# eBox_3G_SIM.net
KiCad netlist of a schematic drawn in Altium Designer
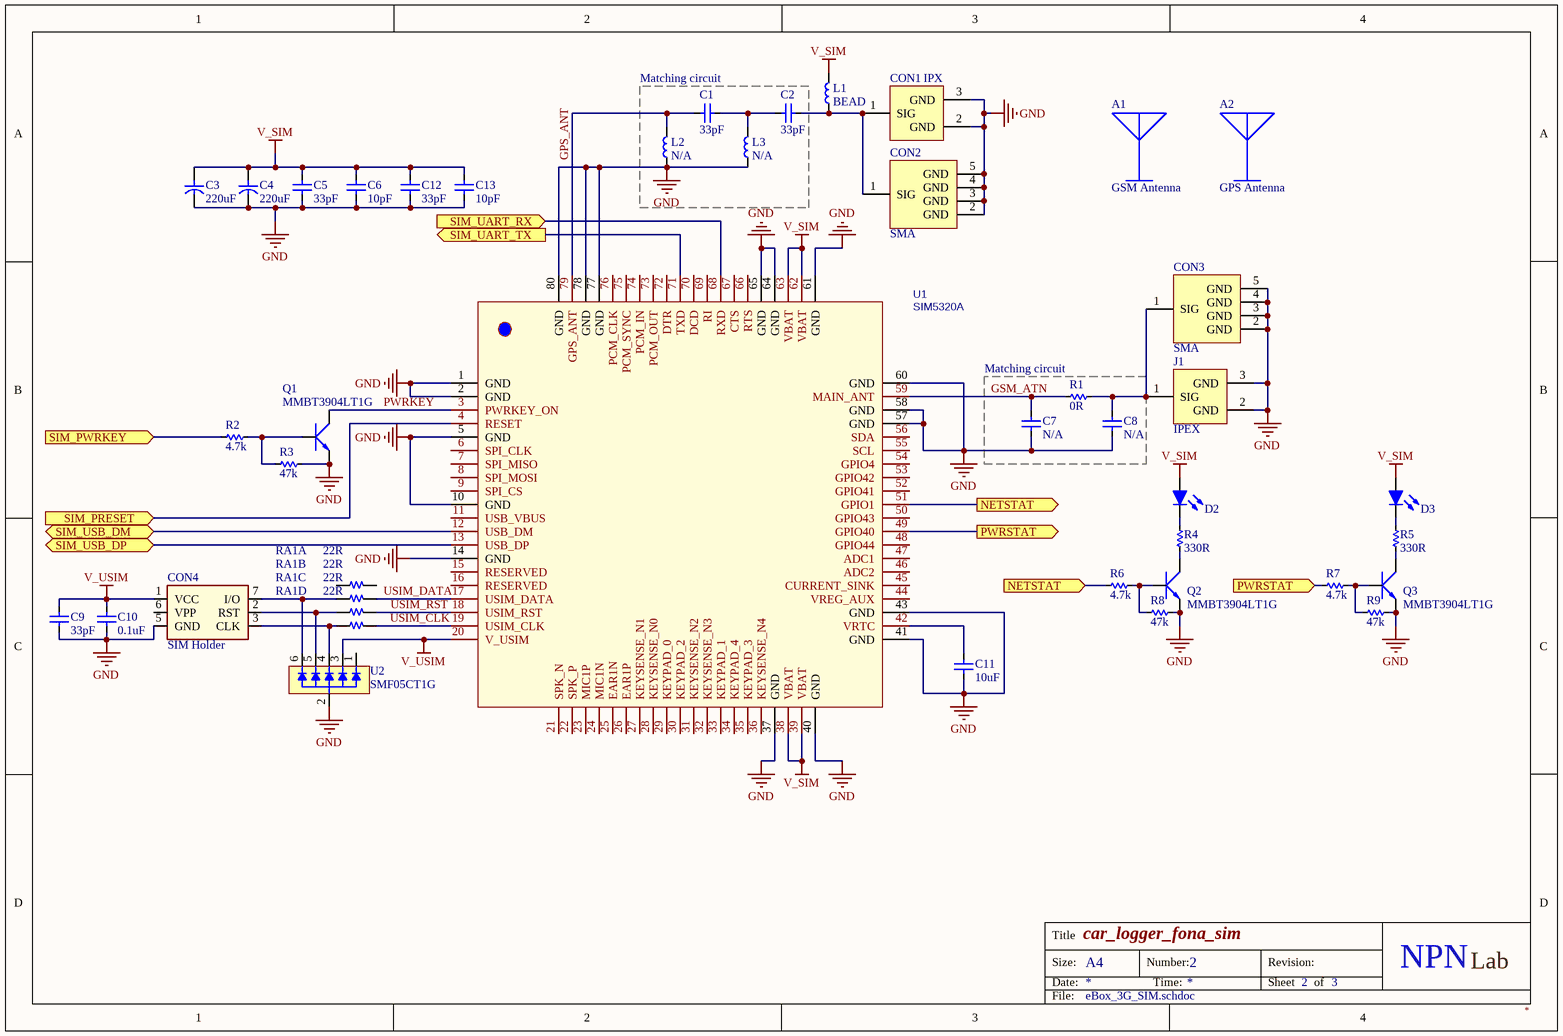
[diagram p0: eBox_3G_SIM.schdoc]

(export (version "E")
  (design (tool "Eeschema 10.0.6"))
  (components
    (comp (ref "A1")
      (value "GSM Antenna")
      (footprint "Antenna")
      (description "Antenna")
      (libsource (lib "car_logger_libs") (part "Antenna"))
    )
    (comp (ref "A2")
      (value "GPS Antenna")
      (footprint "Antenna")
      (description "Antenna")
      (libsource (lib "car_logger_libs") (part "Antenna"))
    )
    (comp (ref "C1")
      (value "33pF")
      (footprint "CC 0603")
      (description "CAP CER 33PF 100V C0G/NP0 0603")
      (fields
        (field (name "MANUFACTURER") "Murata Electronics")
        (field (name "MANUFACTURER PART NUMBER") "GCM1885C2A330JA16D")
      )
      (libsource (lib "car_logger_libs") (part "Capacitor NP"))
    )
    (comp (ref "C2")
      (value "33pF")
      (footprint "CC 0603")
      (description "CAP CER 33PF 100V C0G/NP0 0603")
      (fields
        (field (name "MANUFACTURER") "Murata Electronics")
        (field (name "MANUFACTURER PART NUMBER") "GCM1885C2A330JA16D")
      )
      (libsource (lib "car_logger_libs") (part "Capacitor NP"))
    )
    (comp (ref "C3")
      (value "220uF")
      (footprint "C SMD ALU (D8)")
      (description "CAP TANT POLY 100UF 6.3V 1210")
      (fields
        (field (name "MANUFACTURER") "AVX Corporation")
        (field (name "MANUFACTURER PART NUMBER") "TCJB107M006R0055")
      )
      (libsource (lib "ChipFC_Lib") (part "Capacitor"))
    )
    (comp (ref "C4")
      (value "220uF")
      (footprint "C SMD ALU (D8)")
      (description "CAP TANT POLY 100UF 6.3V 1210")
      (fields
        (field (name "MANUFACTURER") "AVX Corporation")
        (field (name "MANUFACTURER PART NUMBER") "TCJB107M006R0055")
      )
      (libsource (lib "ChipFC_Lib") (part "Capacitor"))
    )
    (comp (ref "C5")
      (value "33pF")
      (footprint "CC 0603")
      (description "CAP CER 33PF 100V C0G/NP0 0603")
      (fields
        (field (name "MANUFACTURER") "Murata Electronics")
        (field (name "MANUFACTURER PART NUMBER") "GCM1885C2A330JA16D")
      )
      (libsource (lib "car_logger_libs") (part "Capacitor NP"))
    )
    (comp (ref "C6")
      (value "10pF")
      (footprint "CC 0603")
      (description "CAP CER 10PF 100V C0G/NP0 0603")
      (fields
        (field (name "MANUFACTURER") "Murata Electronics")
        (field (name "MANUFACTURER PART NUMBER") "GCM1885C2A100JA16D")
      )
      (libsource (lib "car_logger_libs") (part "Capacitor NP"))
    )
    (comp (ref "C7")
      (value "N/A")
      (footprint "CC 0603")
      (description "CAP N/A")
      (libsource (lib "car_logger_libs") (part "Capacitor NP"))
    )
    (comp (ref "C8")
      (value "N/A")
      (footprint "CC 0603")
      (description "CAP N/A")
      (libsource (lib "car_logger_libs") (part "Capacitor NP"))
    )
    (comp (ref "C9")
      (value "33pF")
      (footprint "CC 0603")
      (description "CAP CER 33PF 100V C0G/NP0 0603")
      (fields
        (field (name "MANUFACTURER") "Murata Electronics")
        (field (name "MANUFACTURER PART NUMBER") "GCM1885C2A330JA16D")
      )
      (libsource (lib "car_logger_libs") (part "Capacitor NP"))
    )
    (comp (ref "C10")
      (value "0.1uF")
      (footprint "CC 0603")
      (description "CAP CER 0.1UF 16V X7R 0603")
      (fields
        (field (name "MANUFACTURER") "Murata Electronics")
        (field (name "MANUFACTURER PART NUMBER") "GCJ188R71C104KA01D")
      )
      (libsource (lib "car_logger_libs") (part "Capacitor NP"))
    )
    (comp (ref "C11")
      (value "10uF")
      (footprint "CC 0805")
      (description "CAP CER 10UF 10V X5R 0603")
      (fields
        (field (name "MANUFACTURER") "Murata Electronics")
        (field (name "MANUFACTURER PART NUMBER") "GRM188R61A106KE69D")
      )
      (libsource (lib "car_logger_libs") (part "Capacitor NP"))
    )
    (comp (ref "C12")
      (value "33pF")
      (footprint "CC 0603")
      (description "CAP CER 33PF 100V C0G/NP0 0603")
      (fields
        (field (name "MANUFACTURER") "Murata Electronics")
        (field (name "MANUFACTURER PART NUMBER") "GCM1885C2A330JA16D")
      )
      (libsource (lib "car_logger_libs") (part "Capacitor NP"))
    )
    (comp (ref "C13")
      (value "10pF")
      (footprint "CC 0603")
      (description "CAP CER 10PF 100V C0G/NP0 0603")
      (fields
        (field (name "MANUFACTURER") "Murata Electronics")
        (field (name "MANUFACTURER PART NUMBER") "GCM1885C2A100JA16D")
      )
      (libsource (lib "car_logger_libs") (part "Capacitor NP"))
    )
    (comp (ref "CON1")
      (value "IPX")
      (footprint "CONN/IPX/SMD")
      (libsource (lib "chipfc_altium_libs") (part "CON IPX"))
    )
    (comp (ref "CON2")
      (value "SMA")
      (footprint "CONN/SMA/RA")
      (description "SMA connectors")
      (libsource (lib "chipfc_altium_libs") (part "CON SMA"))
    )
    (comp (ref "CON3")
      (value "SMA")
      (footprint "CONN/SMA/RA")
      (description "SMA connectors")
      (libsource (lib "chipfc_altium_libs") (part "CON SMA"))
    )
    (comp (ref "CON4")
      (value "SIM Holder")
      (footprint "CON SIM Holder C707")
      (description "SIM Card holder, 6 pins")
      (libsource (lib "chipfc_altium_libs") (part "SIM holder 6 pin"))
    )
    (comp (ref "D2")
      (value "LED GREEN")
      (footprint "Led 0603 - green")
      (description "LED GREEN DIFFUSED 0603 SMD")
      (fields
        (field (name "MANUFACTURER") "Rohm Semiconductor")
        (field (name "MANUFACTURER PART NUMBER") "SML-D12P8WT86")
      )
      (libsource (lib "ChipFC_Lib") (part "Led"))
    )
    (comp (ref "D3")
      (value "LED RED")
      (footprint "Led 0603 - red")
      (description "LED RED DIFFUSED 0603 SMD")
      (fields
        (field (name "MANUFACTURER") "Rohm Semiconductor")
        (field (name "MANUFACTURER PART NUMBER") "SML-D12U8WT86")
      )
      (libsource (lib "ChipFC_Lib") (part "Led"))
    )
    (comp (ref "J1")
      (value "IPEX")
      (footprint "CONN/IPX/SMD")
      (description "CONN UMC RCPT STR 50 OHM SMD")
      (fields
        (field (name "MANUFACTURER") "Taoglas Limited")
        (field (name "MANUFACTURER PART NUMBER") "RECE.20279.001E.01")
      )
      (libsource (lib "ChipFC_Lib") (part "CON IPX"))
    )
    (comp (ref "L1")
      (value "BEAD")
      (footprint "LL 0603")
      (description "FERRITE BEAD 30 OHM 0603 1LN")
      (fields
        (field (name "MANUFACTURER") "Vishay Dale")
        (field (name "MANUFACTURER PART NUMBER") "ILBB0603ER300V")
      )
      (libsource (lib "car_logger_libs") (part "Inductor"))
    )
    (comp (ref "L2")
      (value "N/A")
      (footprint "LL 0603")
      (description "IND N/A")
      (libsource (lib "car_logger_libs") (part "Inductor"))
    )
    (comp (ref "L3")
      (value "N/A")
      (footprint "LL 0603")
      (description "IND N/A")
      (libsource (lib "car_logger_libs") (part "Inductor"))
    )
    (comp (ref "Q1")
      (value "MMBT3904LT1G")
      (footprint "SOT-23")
      (description "TRANS NPN 40V 0.2A SOT23")
      (fields (field (name "MANUFACTURER") "ON Semiconductor"))
      (libsource (lib "car_logger_libs") (part "MMBT3904LT1G"))
    )
    (comp (ref "Q2")
      (value "MMBT3904LT1G")
      (footprint "SOT-23")
      (description "TRANS NPN 40V 0.2A SOT23")
      (fields (field (name "MANUFACTURER") "ON Semiconductor"))
      (libsource (lib "car_logger_libs") (part "MMBT3904LT1G"))
    )
    (comp (ref "Q3")
      (value "MMBT3904LT1G")
      (footprint "SOT-23")
      (description "TRANS NPN 40V 0.2A SOT23")
      (fields (field (name "MANUFACTURER") "ON Semiconductor"))
      (libsource (lib "car_logger_libs") (part "MMBT3904LT1G"))
    )
    (comp (ref "R1")
      (value "0R")
      (footprint "RR 0603")
      (description "RES SMD 0 OHM JUMPER 1/10W 0603")
      (fields
        (field (name "MANUFACTURER") "Panasonic Industrial Devices")
        (field (name "MANUFACTURER PART NUMBER") "ERJ-3GEY0R00V")
      )
      (libsource (lib "car_logger_libs") (part "Resistors"))
    )
    (comp (ref "R2")
      (value "4.7k")
      (footprint "RR 0603")
      (description "RES SMD 4.7K OHM 1% 1/10W 0603")
      (fields
        (field (name "MANUFACTURER") "Panasonic Industrial Devices")
        (field (name "MANUFACTURER PART NUMBER") "ERJ-3EKF4701V")
      )
      (libsource (lib "car_logger_libs") (part "Resistors"))
    )
    (comp (ref "R3")
      (value "47k")
      (footprint "RR 0603")
      (description "RES SMD 47K OHM 5% 1/10W 0603")
      (fields
        (field (name "MANUFACTURER") "Panasonic Industrial Devices")
        (field (name "MANUFACTURER PART NUMBER") "ERJ-3GEYJ473V")
      )
      (libsource (lib "car_logger_libs") (part "Resistors"))
    )
    (comp (ref "R4")
      (value "330R")
      (footprint "RR 0603")
      (description "RES SMD 330 OHM 5% 1/10W 0603")
      (fields
        (field (name "MANUFACTURER") "Panasonic Industrial Devices")
        (field (name "MANUFACTURER PART NUMBER") "ERJ-3GEYJ331V")
      )
      (libsource (lib "car_logger_libs") (part "Resistors"))
    )
    (comp (ref "R5")
      (value "330R")
      (footprint "RR 0603")
      (description "RES SMD 330 OHM 5% 1/10W 0603")
      (fields
        (field (name "MANUFACTURER") "Panasonic Industrial Devices")
        (field (name "MANUFACTURER PART NUMBER") "ERJ-3GEYJ331V")
      )
      (libsource (lib "car_logger_libs") (part "Resistors"))
    )
    (comp (ref "R6")
      (value "4.7k")
      (footprint "RR 0603")
      (description "RES SMD 4.7K OHM 1% 1/10W 0603")
      (fields
        (field (name "MANUFACTURER") "Panasonic Industrial Devices")
        (field (name "MANUFACTURER PART NUMBER") "ERJ-3EKF4701V")
      )
      (libsource (lib "car_logger_libs") (part "Resistors"))
    )
    (comp (ref "R7")
      (value "4.7k")
      (footprint "RR 0603")
      (description "RES SMD 4.7K OHM 1% 1/10W 0603")
      (fields
        (field (name "MANUFACTURER") "Panasonic Industrial Devices")
        (field (name "MANUFACTURER PART NUMBER") "ERJ-3EKF4701V")
      )
      (libsource (lib "car_logger_libs") (part "Resistors"))
    )
    (comp (ref "R8")
      (value "47k")
      (footprint "RR 0603")
      (description "RES SMD 47K OHM 5% 1/10W 0603")
      (fields
        (field (name "MANUFACTURER") "Panasonic Industrial Devices")
        (field (name "MANUFACTURER PART NUMBER") "ERJ-3GEYJ473V")
      )
      (libsource (lib "car_logger_libs") (part "Resistors"))
    )
    (comp (ref "R9")
      (value "47k")
      (footprint "RR 0603")
      (description "RES SMD 47K OHM 5% 1/10W 0603")
      (fields
        (field (name "MANUFACTURER") "Panasonic Industrial Devices")
        (field (name "MANUFACTURER PART NUMBER") "ERJ-3GEYJ473V")
      )
      (libsource (lib "car_logger_libs") (part "Resistors"))
    )
    (comp (ref "RA1")
      (value "22R")
      (footprint "RAx4 1206 (3216)")
      (libsource (lib "chipfc_altium_libs") (part "Resistor Array x4"))
    )
    (comp (ref "U1")
      (value "SIM5320A")
      (footprint "SIM5320")
      (libsource (lib "car_logger_libs") (part "SIM5320A"))
    )
    (comp (ref "U2")
      (value "SMF05CT1G")
      (footprint "SOT-363-6")
      (description "TVS DIODE 5V 12.5V SC88")
      (fields (field (name "MANUFACTURER") "ON Semiconductor"))
      (libsource (lib "car_logger_libs") (part "SMF05C"))
    )
  )
  (nets
    (net (code "1") (name "/GPS_ANT") (class "Default")
      (node (ref "C1") (pin "2") (pinfunction "2_2") (pintype "passive"))
      (node (ref "L2") (pin "2") (pinfunction "2_2") (pintype "passive"))
      (node (ref "U1") (pin "79") (pinfunction "GPS_ANT_79") (pintype "passive"))
    )
    (net (code "2") (name "/GSM_ATN") (class "Default")
      (node (ref "C7") (pin "2") (pinfunction "2_2") (pintype "passive"))
      (node (ref "R1") (pin "2") (pinfunction "2_2") (pintype "passive"))
      (node (ref "U1") (pin "59") (pinfunction "MAIN_ANT_59") (pintype "passive"))
    )
    (net (code "3") (name "/NETSTAT") (class "Default")
      (node (ref "R6") (pin "1") (pinfunction "1_1") (pintype "passive"))
      (node (ref "U1") (pin "51") (pinfunction "GPIO1_51") (pintype "passive"))
    )
    (net (code "4") (name "/PWRKEY") (class "Default")
      (node (ref "Q1") (pin "3") (pinfunction "C_3") (pintype "passive"))
      (node (ref "U1") (pin "3") (pinfunction "PWRKEY_ON_3") (pintype "passive"))
    )
    (net (code "5") (name "/PWRSTAT") (class "Default")
      (node (ref "R7") (pin "1") (pinfunction "1_1") (pintype "passive"))
      (node (ref "U1") (pin "49") (pinfunction "GPIO40_49") (pintype "passive"))
    )
    (net (code "6") (name "/SIM_PRESET") (class "Default")
      (node (ref "U1") (pin "4") (pinfunction "RESET_4") (pintype "passive"))
    )
    (net (code "7") (name "/SIM_PWRKEY") (class "Default")
      (node (ref "R2") (pin "1") (pinfunction "1_1") (pintype "passive"))
    )
    (net (code "8") (name "/SIM_UART_RX") (class "Default")
      (node (ref "U1") (pin "68") (pinfunction "RXD_68") (pintype "passive"))
    )
    (net (code "9") (name "/SIM_UART_TX") (class "Default")
      (node (ref "U1") (pin "71") (pinfunction "TXD_71") (pintype "passive"))
    )
    (net (code "10") (name "/SIM_USB_DM") (class "Default")
      (node (ref "U1") (pin "12") (pinfunction "USB_DM_12") (pintype "passive"))
    )
    (net (code "11") (name "/SIM_USB_DP") (class "Default")
      (node (ref "U1") (pin "13") (pinfunction "USB_DP_13") (pintype "passive"))
    )
    (net (code "12") (name "/USIM_CLK") (class "Default")
      (node (ref "RA1") (pin "5") (pinfunction "5_5") (pintype "passive"))
      (node (ref "U1") (pin "19") (pinfunction "USIM_CLK_19") (pintype "passive"))
    )
    (net (code "13") (name "/USIM_DATA") (class "Default")
      (node (ref "RA1") (pin "7") (pinfunction "7_7") (pintype "passive"))
      (node (ref "U1") (pin "17") (pinfunction "USIM_DATA_17") (pintype "passive"))
    )
    (net (code "14") (name "/USIM_RST") (class "Default")
      (node (ref "RA1") (pin "6") (pinfunction "6_6") (pintype "passive"))
      (node (ref "U1") (pin "18") (pinfunction "USIM_RST_18") (pintype "passive"))
    )
    (net (code "15") (name "GND") (class "Default")
      (node (ref "C10") (pin "2") (pinfunction "2_2") (pintype "passive"))
      (node (ref "C11") (pin "1") (pinfunction "1_1") (pintype "passive"))
      (node (ref "C12") (pin "1") (pinfunction "1_1") (pintype "passive"))
      (node (ref "C13") (pin "1") (pinfunction "1_1") (pintype "passive"))
      (node (ref "C3") (pin "2") (pinfunction "2_2") (pintype "passive"))
      (node (ref "C4") (pin "2") (pinfunction "2_2") (pintype "passive"))
      (node (ref "C5") (pin "1") (pinfunction "1_1") (pintype "passive"))
      (node (ref "C6") (pin "1") (pinfunction "1_1") (pintype "passive"))
      (node (ref "C7") (pin "1") (pinfunction "1_1") (pintype "passive"))
      (node (ref "C8") (pin "1") (pinfunction "1_1") (pintype "passive"))
      (node (ref "C9") (pin "2") (pinfunction "2_2") (pintype "passive"))
      (node (ref "CON1") (pin "2") (pinfunction "GND_2") (pintype "passive"))
      (node (ref "CON1") (pin "3") (pinfunction "GND_3") (pintype "passive"))
      (node (ref "CON2") (pin "2") (pinfunction "GND_2") (pintype "passive"))
      (node (ref "CON2") (pin "3") (pinfunction "GND_3") (pintype "passive"))
      (node (ref "CON2") (pin "4") (pinfunction "GND_4") (pintype "passive"))
      (node (ref "CON2") (pin "5") (pinfunction "GND_5") (pintype "passive"))
      (node (ref "CON3") (pin "2") (pinfunction "GND_2") (pintype "passive"))
      (node (ref "CON3") (pin "3") (pinfunction "GND_3") (pintype "passive"))
      (node (ref "CON3") (pin "4") (pinfunction "GND_4") (pintype "passive"))
      (node (ref "CON3") (pin "5") (pinfunction "GND_5") (pintype "passive"))
      (node (ref "CON4") (pin "5") (pinfunction "GND_5") (pintype "power_in"))
      (node (ref "J1") (pin "2") (pinfunction "GND_2") (pintype "passive"))
      (node (ref "J1") (pin "3") (pinfunction "GND_3") (pintype "passive"))
      (node (ref "L2") (pin "1") (pinfunction "1_1") (pintype "passive"))
      (node (ref "L3") (pin "1") (pinfunction "1_1") (pintype "passive"))
      (node (ref "Q1") (pin "2") (pinfunction "E_2") (pintype "passive"))
      (node (ref "Q2") (pin "2") (pinfunction "E_2") (pintype "passive"))
      (node (ref "Q3") (pin "2") (pinfunction "E_2") (pintype "passive"))
      (node (ref "R3") (pin "2") (pinfunction "2_2") (pintype "passive"))
      (node (ref "R8") (pin "2") (pinfunction "2_2") (pintype "passive"))
      (node (ref "R9") (pin "2") (pinfunction "2_2") (pintype "passive"))
      (node (ref "U1") (pin "1") (pinfunction "GND_1") (pintype "passive"))
      (node (ref "U1") (pin "10") (pinfunction "GND_10") (pintype "passive"))
      (node (ref "U1") (pin "14") (pinfunction "GND_14") (pintype "passive"))
      (node (ref "U1") (pin "2") (pinfunction "GND_2") (pintype "passive"))
      (node (ref "U1") (pin "37") (pinfunction "GND_37") (pintype "passive"))
      (node (ref "U1") (pin "40") (pinfunction "GND_40") (pintype "passive"))
      (node (ref "U1") (pin "41") (pinfunction "GND_41") (pintype "passive"))
      (node (ref "U1") (pin "43") (pinfunction "GND_43") (pintype "passive"))
      (node (ref "U1") (pin "5") (pinfunction "GND_5") (pintype "passive"))
      (node (ref "U1") (pin "57") (pinfunction "GND_57") (pintype "passive"))
      (node (ref "U1") (pin "58") (pinfunction "GND_58") (pintype "passive"))
      (node (ref "U1") (pin "60") (pinfunction "GND_60") (pintype "passive"))
      (node (ref "U1") (pin "61") (pinfunction "GND_61") (pintype "passive"))
      (node (ref "U1") (pin "64") (pinfunction "GND_64") (pintype "passive"))
      (node (ref "U1") (pin "65") (pinfunction "GND_65") (pintype "passive"))
      (node (ref "U1") (pin "77") (pinfunction "GND_77") (pintype "passive"))
      (node (ref "U1") (pin "78") (pinfunction "GND_78") (pintype "passive"))
      (node (ref "U1") (pin "80") (pinfunction "GND_80") (pintype "passive"))
      (node (ref "U2") (pin "2") (pinfunction "A_2") (pintype "passive"))
    )
    (net (code "16") (name "Net-(C1-Pad1)") (class "Default")
      (node (ref "C1") (pin "1") (pinfunction "1_1") (pintype "passive"))
      (node (ref "C2") (pin "2") (pinfunction "2_2") (pintype "passive"))
      (node (ref "L3") (pin "2") (pinfunction "2_2") (pintype "passive"))
    )
    (net (code "17") (name "Net-(CON1-SIG)") (class "Default")
      (node (ref "C2") (pin "1") (pinfunction "1_1") (pintype "passive"))
      (node (ref "CON1") (pin "1") (pinfunction "SIG_1") (pintype "passive"))
      (node (ref "CON2") (pin "1") (pinfunction "SIG_1") (pintype "passive"))
      (node (ref "L1") (pin "1") (pinfunction "1_1") (pintype "passive"))
    )
    (net (code "18") (name "Net-(CON3-SIG)") (class "Default")
      (node (ref "C8") (pin "2") (pinfunction "2_2") (pintype "passive"))
      (node (ref "CON3") (pin "1") (pinfunction "SIG_1") (pintype "passive"))
      (node (ref "J1") (pin "1") (pinfunction "SIG_1") (pintype "passive"))
      (node (ref "R1") (pin "1") (pinfunction "1_1") (pintype "passive"))
    )
    (net (code "19") (name "Net-(CON4-CLK)") (class "Default")
      (node (ref "CON4") (pin "3") (pinfunction "CLK_3") (pintype "passive"))
      (node (ref "RA1") (pin "4") (pinfunction "4_4") (pintype "passive"))
      (node (ref "U2") (pin "4") (pinfunction "K4_4") (pintype "passive"))
    )
    (net (code "20") (name "Net-(CON4-I{slash}O)") (class "Default")
      (node (ref "CON4") (pin "7") (pinfunction "I/O_7") (pintype "passive"))
      (node (ref "RA1") (pin "2") (pinfunction "2_2") (pintype "passive"))
      (node (ref "U2") (pin "6") (pinfunction "K6_6") (pintype "passive"))
    )
    (net (code "21") (name "Net-(CON4-RST)") (class "Default")
      (node (ref "CON4") (pin "2") (pinfunction "RST_2") (pintype "passive"))
      (node (ref "RA1") (pin "3") (pinfunction "3_3") (pintype "passive"))
      (node (ref "U2") (pin "5") (pinfunction "K5_5") (pintype "passive"))
    )
    (net (code "22") (name "Net-(D2-K)") (class "Default")
      (node (ref "D2") (pin "2") (pinfunction "K_2") (pintype "passive"))
      (node (ref "R4") (pin "2") (pinfunction "2_2") (pintype "passive"))
    )
    (net (code "23") (name "Net-(D3-K)") (class "Default")
      (node (ref "D3") (pin "2") (pinfunction "K_2") (pintype "passive"))
      (node (ref "R5") (pin "2") (pinfunction "2_2") (pintype "passive"))
    )
    (net (code "24") (name "Net-(Q1-B)") (class "Default")
      (node (ref "Q1") (pin "1") (pinfunction "B_1") (pintype "passive"))
      (node (ref "R2") (pin "2") (pinfunction "2_2") (pintype "passive"))
      (node (ref "R3") (pin "1") (pinfunction "1_1") (pintype "passive"))
    )
    (net (code "25") (name "Net-(Q2-B)") (class "Default")
      (node (ref "Q2") (pin "1") (pinfunction "B_1") (pintype "passive"))
      (node (ref "R6") (pin "2") (pinfunction "2_2") (pintype "passive"))
      (node (ref "R8") (pin "1") (pinfunction "1_1") (pintype "passive"))
    )
    (net (code "26") (name "Net-(Q2-C)") (class "Default")
      (node (ref "Q2") (pin "3") (pinfunction "C_3") (pintype "passive"))
      (node (ref "R4") (pin "1") (pinfunction "1_1") (pintype "passive"))
    )
    (net (code "27") (name "Net-(Q3-B)") (class "Default")
      (node (ref "Q3") (pin "1") (pinfunction "B_1") (pintype "passive"))
      (node (ref "R7") (pin "2") (pinfunction "2_2") (pintype "passive"))
      (node (ref "R9") (pin "1") (pinfunction "1_1") (pintype "passive"))
    )
    (net (code "28") (name "Net-(Q3-C)") (class "Default")
      (node (ref "Q3") (pin "3") (pinfunction "C_3") (pintype "passive"))
      (node (ref "R5") (pin "1") (pinfunction "1_1") (pintype "passive"))
    )
    (net (code "29") (name "Net-(U1-VRTC)") (class "Default")
      (node (ref "C11") (pin "2") (pinfunction "2_2") (pintype "passive"))
      (node (ref "U1") (pin "42") (pinfunction "VRTC_42") (pintype "passive"))
    )
    (net (code "30") (name "V_SIM") (class "Default")
      (node (ref "C12") (pin "2") (pinfunction "2_2") (pintype "passive"))
      (node (ref "C13") (pin "2") (pinfunction "2_2") (pintype "passive"))
      (node (ref "C3") (pin "1") (pinfunction "1_1") (pintype "passive"))
      (node (ref "C4") (pin "1") (pinfunction "1_1") (pintype "passive"))
      (node (ref "C5") (pin "2") (pinfunction "2_2") (pintype "passive"))
      (node (ref "C6") (pin "2") (pinfunction "2_2") (pintype "passive"))
      (node (ref "D2") (pin "1") (pinfunction "A_1") (pintype "passive"))
      (node (ref "D3") (pin "1") (pinfunction "A_1") (pintype "passive"))
      (node (ref "L1") (pin "2") (pinfunction "2_2") (pintype "passive"))
      (node (ref "U1") (pin "38") (pinfunction "VBAT_38") (pintype "passive"))
      (node (ref "U1") (pin "39") (pinfunction "VBAT_39") (pintype "passive"))
      (node (ref "U1") (pin "62") (pinfunction "VBAT_62") (pintype "passive"))
      (node (ref "U1") (pin "63") (pinfunction "VBAT_63") (pintype "passive"))
    )
    (net (code "31") (name "V_USIM") (class "Default")
      (node (ref "C10") (pin "1") (pinfunction "1_1") (pintype "passive"))
      (node (ref "C9") (pin "1") (pinfunction "1_1") (pintype "passive"))
      (node (ref "CON4") (pin "1") (pinfunction "VCC_1") (pintype "power_in"))
      (node (ref "U1") (pin "20") (pinfunction "V_USIM_20") (pintype "passive"))
      (node (ref "U2") (pin "3") (pinfunction "K3_3") (pintype "passive"))
    )
    (net (code "32") (name "unconnected-(CON4-VPP-Pad6)") (class "Default")
      (node (ref "CON4") (pin "6") (pinfunction "VPP_6") (pintype "passive"))
    )
    (net (code "33") (name "unconnected-(RA1-Pad1)") (class "Default")
      (node (ref "RA1") (pin "1") (pinfunction "1_1") (pintype "passive"))
    )
    (net (code "34") (name "unconnected-(RA1-Pad8)") (class "Default")
      (node (ref "RA1") (pin "8") (pinfunction "8_8") (pintype "passive"))
    )
    (net (code "35") (name "unconnected-(U1-ADC1-Pad47)") (class "Default")
      (node (ref "U1") (pin "47") (pinfunction "ADC1_47") (pintype "passive"))
    )
    (net (code "36") (name "unconnected-(U1-ADC2-Pad46)") (class "Default")
      (node (ref "U1") (pin "46") (pinfunction "ADC2_46") (pintype "passive"))
    )
    (net (code "37") (name "unconnected-(U1-CTS-Pad67)") (class "Default")
      (node (ref "U1") (pin "67") (pinfunction "CTS_67") (pintype "passive"))
    )
    (net (code "38") (name "unconnected-(U1-CURRENT_SINK-Pad45)") (class "Default")
      (node (ref "U1") (pin "45") (pinfunction "CURRENT_SINK_45") (pintype "passive"))
    )
    (net (code "39") (name "unconnected-(U1-DCD-Pad70)") (class "Default")
      (node (ref "U1") (pin "70") (pinfunction "DCD_70") (pintype "passive"))
    )
    (net (code "40") (name "unconnected-(U1-DTR-Pad72)") (class "Default")
      (node (ref "U1") (pin "72") (pinfunction "DTR_72") (pintype "passive"))
    )
    (net (code "41") (name "unconnected-(U1-EAR1N-Pad25)") (class "Default")
      (node (ref "U1") (pin "25") (pinfunction "EAR1N_25") (pintype "passive"))
    )
    (net (code "42") (name "unconnected-(U1-EAR1P-Pad26)") (class "Default")
      (node (ref "U1") (pin "26") (pinfunction "EAR1P_26") (pintype "passive"))
    )
    (net (code "43") (name "unconnected-(U1-GPIO4-Pad54)") (class "Default")
      (node (ref "U1") (pin "54") (pinfunction "GPIO4_54") (pintype "passive"))
    )
    (net (code "44") (name "unconnected-(U1-GPIO41-Pad52)") (class "Default")
      (node (ref "U1") (pin "52") (pinfunction "GPIO41_52") (pintype "passive"))
    )
    (net (code "45") (name "unconnected-(U1-GPIO42-Pad53)") (class "Default")
      (node (ref "U1") (pin "53") (pinfunction "GPIO42_53") (pintype "passive"))
    )
    (net (code "46") (name "unconnected-(U1-GPIO43-Pad50)") (class "Default")
      (node (ref "U1") (pin "50") (pinfunction "GPIO43_50") (pintype "passive"))
    )
    (net (code "47") (name "unconnected-(U1-GPIO44-Pad48)") (class "Default")
      (node (ref "U1") (pin "48") (pinfunction "GPIO44_48") (pintype "passive"))
    )
    (net (code "48") (name "unconnected-(U1-KEYPAD_0-Pad29)") (class "Default")
      (node (ref "U1") (pin "29") (pinfunction "KEYPAD_0_29") (pintype "passive"))
    )
    (net (code "49") (name "unconnected-(U1-KEYPAD_1-Pad33)") (class "Default")
      (node (ref "U1") (pin "33") (pinfunction "KEYPAD_1_33") (pintype "passive"))
    )
    (net (code "50") (name "unconnected-(U1-KEYPAD_2-Pad30)") (class "Default")
      (node (ref "U1") (pin "30") (pinfunction "KEYPAD_2_30") (pintype "passive"))
    )
    (net (code "51") (name "unconnected-(U1-KEYPAD_3-Pad35)") (class "Default")
      (node (ref "U1") (pin "35") (pinfunction "KEYPAD_3_35") (pintype "passive"))
    )
    (net (code "52") (name "unconnected-(U1-KEYPAD_4-Pad34)") (class "Default")
      (node (ref "U1") (pin "34") (pinfunction "KEYPAD_4_34") (pintype "passive"))
    )
    (net (code "53") (name "unconnected-(U1-KEYSENSE_N0-Pad28)") (class "Default")
      (node (ref "U1") (pin "28") (pinfunction "KEYSENSE_N0_28") (pintype "passive"))
    )
    (net (code "54") (name "unconnected-(U1-KEYSENSE_N1-Pad27)") (class "Default")
      (node (ref "U1") (pin "27") (pinfunction "KEYSENSE_N1_27") (pintype "passive"))
    )
    (net (code "55") (name "unconnected-(U1-KEYSENSE_N2-Pad31)") (class "Default")
      (node (ref "U1") (pin "31") (pinfunction "KEYSENSE_N2_31") (pintype "passive"))
    )
    (net (code "56") (name "unconnected-(U1-KEYSENSE_N3-Pad32)") (class "Default")
      (node (ref "U1") (pin "32") (pinfunction "KEYSENSE_N3_32") (pintype "passive"))
    )
    (net (code "57") (name "unconnected-(U1-KEYSENSE_N4-Pad36)") (class "Default")
      (node (ref "U1") (pin "36") (pinfunction "KEYSENSE_N4_36") (pintype "passive"))
    )
    (net (code "58") (name "unconnected-(U1-MIC1N-Pad24)") (class "Default")
      (node (ref "U1") (pin "24") (pinfunction "MIC1N_24") (pintype "passive"))
    )
    (net (code "59") (name "unconnected-(U1-MIC1P-Pad23)") (class "Default")
      (node (ref "U1") (pin "23") (pinfunction "MIC1P_23") (pintype "passive"))
    )
    (net (code "60") (name "unconnected-(U1-PCM_CLK-Pad76)") (class "Default")
      (node (ref "U1") (pin "76") (pinfunction "PCM_CLK_76") (pintype "passive"))
    )
    (net (code "61") (name "unconnected-(U1-PCM_IN-Pad74)") (class "Default")
      (node (ref "U1") (pin "74") (pinfunction "PCM_IN_74") (pintype "passive"))
    )
    (net (code "62") (name "unconnected-(U1-PCM_OUT-Pad73)") (class "Default")
      (node (ref "U1") (pin "73") (pinfunction "PCM_OUT_73") (pintype "passive"))
    )
    (net (code "63") (name "unconnected-(U1-PCM_SYNC-Pad75)") (class "Default")
      (node (ref "U1") (pin "75") (pinfunction "PCM_SYNC_75") (pintype "passive"))
    )
    (net (code "64") (name "unconnected-(U1-RESERVED-Pad15)") (class "Default")
      (node (ref "U1") (pin "15") (pinfunction "RESERVED_15") (pintype "passive"))
    )
    (net (code "65") (name "unconnected-(U1-RESERVED-Pad16)") (class "Default")
      (node (ref "U1") (pin "16") (pinfunction "RESERVED_16") (pintype "passive"))
    )
    (net (code "66") (name "unconnected-(U1-RI-Pad69)") (class "Default")
      (node (ref "U1") (pin "69") (pinfunction "RI_69") (pintype "passive"))
    )
    (net (code "67") (name "unconnected-(U1-RTS-Pad66)") (class "Default")
      (node (ref "U1") (pin "66") (pinfunction "RTS_66") (pintype "passive"))
    )
    (net (code "68") (name "unconnected-(U1-SCL-Pad55)") (class "Default")
      (node (ref "U1") (pin "55") (pinfunction "SCL_55") (pintype "passive"))
    )
    (net (code "69") (name "unconnected-(U1-SDA-Pad56)") (class "Default")
      (node (ref "U1") (pin "56") (pinfunction "SDA_56") (pintype "passive"))
    )
    (net (code "70") (name "unconnected-(U1-SPI_CLK-Pad6)") (class "Default")
      (node (ref "U1") (pin "6") (pinfunction "SPI_CLK_6") (pintype "passive"))
    )
    (net (code "71") (name "unconnected-(U1-SPI_CS-Pad9)") (class "Default")
      (node (ref "U1") (pin "9") (pinfunction "SPI_CS_9") (pintype "passive"))
    )
    (net (code "72") (name "unconnected-(U1-SPI_MISO-Pad7)") (class "Default")
      (node (ref "U1") (pin "7") (pinfunction "SPI_MISO_7") (pintype "passive"))
    )
    (net (code "73") (name "unconnected-(U1-SPI_MOSI-Pad8)") (class "Default")
      (node (ref "U1") (pin "8") (pinfunction "SPI_MOSI_8") (pintype "passive"))
    )
    (net (code "74") (name "unconnected-(U1-SPK_N-Pad21)") (class "Default")
      (node (ref "U1") (pin "21") (pinfunction "SPK_N_21") (pintype "passive"))
    )
    (net (code "75") (name "unconnected-(U1-SPK_P-Pad22)") (class "Default")
      (node (ref "U1") (pin "22") (pinfunction "SPK_P_22") (pintype "passive"))
    )
    (net (code "76") (name "unconnected-(U1-USB_VBUS-Pad11)") (class "Default")
      (node (ref "U1") (pin "11") (pinfunction "USB_VBUS_11") (pintype "passive"))
    )
    (net (code "77") (name "unconnected-(U1-VREG_AUX-Pad44)") (class "Default")
      (node (ref "U1") (pin "44") (pinfunction "VREG_AUX_44") (pintype "passive"))
    )
    (net (code "78") (name "unconnected-(U2-K1-Pad1)") (class "Default")
      (node (ref "U2") (pin "1") (pinfunction "K1_1") (pintype "passive"))
    )
  )
)
